# Buck_converter_demo.net
KiCad netlist of a schematic drawn in Altium Designer
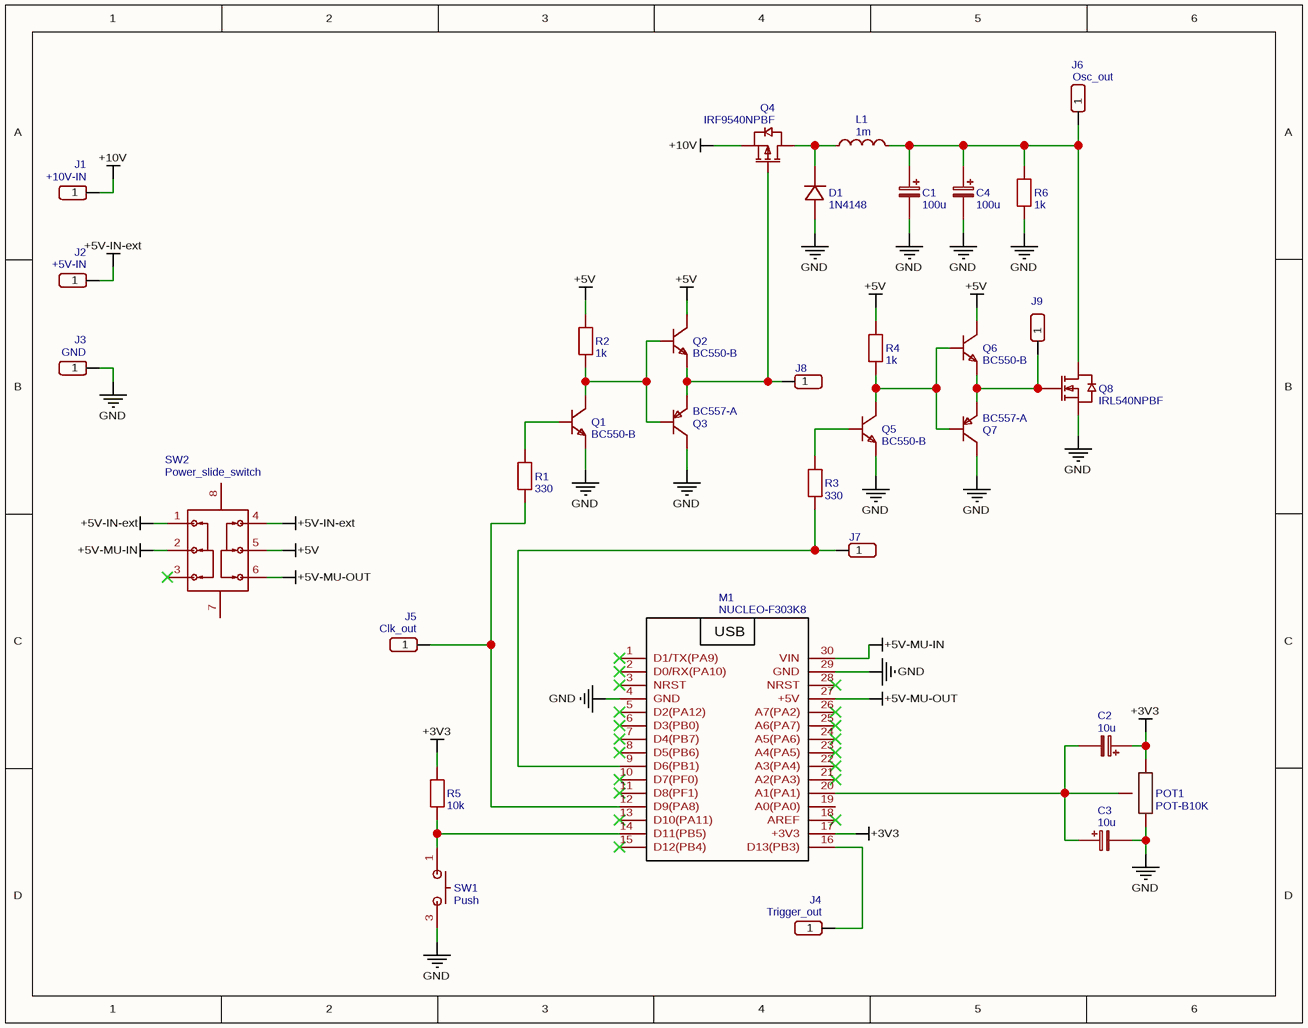
[diagram p0: Buck converter demo.schdoc]

(export (version "E")
  (design (tool "Eeschema 10.0.6"))
  (components
    (comp (ref "C1")
      (value "100u")
      (fields (field (name "CONTRIBUTOR") "LCEDA_Lib"))
      (libsource (lib "altium-import") (part "root_3_100u_"))
    )
    (comp (ref "C2")
      (value "10u")
      (fields (field (name "CONTRIBUTOR") "LCEDA_Lib"))
      (libsource (lib "altium-import") (part "root_2_10u_"))
    )
    (comp (ref "C3")
      (value "10u")
      (fields (field (name "CONTRIBUTOR") "LCEDA_Lib"))
      (libsource (lib "altium-import") (part "root_0_10u_"))
    )
    (comp (ref "C4")
      (value "100u")
      (fields (field (name "CONTRIBUTOR") "LCEDA_Lib"))
      (libsource (lib "altium-import") (part "root_3_100u_"))
    )
    (comp (ref "D1")
      (value "1N4148")
      (fields (field (name "MANUFACTURER") "ST(先科)"))
      (libsource (lib "altium-import") (part "root_1_1N4148_"))
    )
    (comp (ref "J1")
      (value "+10V-IN")
      (fields (field (name "CONTRIBUTOR") "LCEDA_Lib"))
      (libsource (lib "altium-import") (part "root_0_+10V-IN_"))
    )
    (comp (ref "J2")
      (value "+5V-IN")
      (fields (field (name "CONTRIBUTOR") "LCEDA_Lib"))
      (libsource (lib "altium-import") (part "root_0_+5V-IN_"))
    )
    (comp (ref "J3")
      (value "GND")
      (fields (field (name "CONTRIBUTOR") "LCEDA_Lib"))
      (libsource (lib "altium-import") (part "root_0_GND_"))
    )
    (comp (ref "J4")
      (value "Trigger_out")
      (fields (field (name "CONTRIBUTOR") "LCEDA_Lib"))
      (libsource (lib "altium-import") (part "root_0_Trigger_out_"))
    )
    (comp (ref "J5")
      (value "Clk_out")
      (fields (field (name "CONTRIBUTOR") "LCEDA_Lib"))
      (libsource (lib "altium-import") (part "root_0_Clk_out_"))
    )
    (comp (ref "J6")
      (value "Osc_out")
      (fields (field (name "CONTRIBUTOR") "LCEDA_Lib"))
      (libsource (lib "altium-import") (part "root_3_Osc_out_"))
    )
    (comp (ref "J7")
      (value "Osc_out")
      (fields (field (name "CONTRIBUTOR") "LCEDA_Lib"))
      (libsource (lib "altium-import") (part "root_2_Osc_out_"))
    )
    (comp (ref "J8")
      (value "Osc_out")
      (fields (field (name "CONTRIBUTOR") "LCEDA_Lib"))
      (libsource (lib "altium-import") (part "root_2_Osc_out_"))
    )
    (comp (ref "J9")
      (value "Osc_out")
      (fields (field (name "CONTRIBUTOR") "LCEDA_Lib"))
      (libsource (lib "altium-import") (part "root_3_Osc_out_"))
    )
    (comp (ref "L1")
      (value "1m")
      (fields (field (name "CONTRIBUTOR") "LCEDA_Lib"))
      (libsource (lib "altium-import") (part "root_0_1m_"))
    )
    (comp (ref "M1")
      (value "NUCLEO-F303K8")
      (fields (field (name "CONTRIBUTOR") "dleval"))
      (libsource (lib "altium-import") (part "root_0_NUCLEO-F303K8_"))
    )
    (comp (ref "POT1")
      (value "POT-B10K")
      (fields (field (name "CONTRIBUTOR") "Andrius Paurys"))
      (libsource (lib "altium-import") (part "root_1_POT-B10K_"))
    )
    (comp (ref "Q1")
      (value "BC550-B")
      (fields (field (name "MANUFACTURER") "BLUE ROCKET(蓝箭)") (field (name "CONTRIBUTOR") "LCSC"))
      (libsource (lib "altium-import") (part "root_0_BC550-B_"))
    )
    (comp (ref "Q2")
      (value "BC550-B")
      (fields (field (name "MANUFACTURER") "BLUE ROCKET(蓝箭)") (field (name "CONTRIBUTOR") "LCSC"))
      (libsource (lib "altium-import") (part "root_0_BC550-B_"))
    )
    (comp (ref "Q3")
      (value "BC557-A")
      (fields
        (field (name "MANUFACTURER") "onsemi(安森美)")
        (field (name "MANUFACTURER PART") "BC560CTA")
        (field (name "CONTRIBUTOR") "LCSC")
      )
      (libsource (lib "altium-import") (part "root_0_BC557-A_"))
    )
    (comp (ref "Q4")
      (value "IRF9540NPBF")
      (fields (field (name "MANUFACTURER") "Infineon(英飞凌)"))
      (libsource (lib "altium-import") (part "root_1_IRF9540NPBF_"))
    )
    (comp (ref "Q5")
      (value "BC550-B")
      (fields (field (name "MANUFACTURER") "BLUE ROCKET(蓝箭)") (field (name "CONTRIBUTOR") "LCSC"))
      (libsource (lib "altium-import") (part "root_0_BC550-B_"))
    )
    (comp (ref "Q6")
      (value "BC550-B")
      (fields (field (name "MANUFACTURER") "BLUE ROCKET(蓝箭)") (field (name "CONTRIBUTOR") "LCSC"))
      (libsource (lib "altium-import") (part "root_0_BC550-B_"))
    )
    (comp (ref "Q7")
      (value "BC557-A")
      (fields
        (field (name "MANUFACTURER") "onsemi(安森美)")
        (field (name "MANUFACTURER PART") "BC560CTA")
        (field (name "CONTRIBUTOR") "LCSC")
      )
      (libsource (lib "altium-import") (part "root_0_BC557-A_"))
    )
    (comp (ref "Q8")
      (value "IRL540NPBF")
      (fields (field (name "MANUFACTURER") "Infineon(英飞凌)"))
      (libsource (lib "altium-import") (part "root_0_IRL540NPBF_"))
    )
    (comp (ref "R1")
      (value "330")
      (fields (field (name "CONTRIBUTOR") "LCEDA_Lib"))
      (libsource (lib "altium-import") (part "root_1_330_"))
    )
    (comp (ref "R2")
      (value "1k")
      (fields (field (name "CONTRIBUTOR") "LCEDA_Lib"))
      (libsource (lib "altium-import") (part "root_1_1k_"))
    )
    (comp (ref "R3")
      (value "330")
      (fields (field (name "CONTRIBUTOR") "LCEDA_Lib"))
      (libsource (lib "altium-import") (part "root_1_330_"))
    )
    (comp (ref "R4")
      (value "1k")
      (fields (field (name "CONTRIBUTOR") "LCEDA_Lib"))
      (libsource (lib "altium-import") (part "root_1_1k_"))
    )
    (comp (ref "R5")
      (value "10k")
      (fields (field (name "CONTRIBUTOR") "LCEDA_Lib"))
      (libsource (lib "altium-import") (part "root_1_10k_"))
    )
    (comp (ref "R6")
      (value "1k")
      (fields (field (name "CONTRIBUTOR") "LCEDA_Lib"))
      (libsource (lib "altium-import") (part "root_1_1k_"))
    )
    (comp (ref "SW1")
      (value "Push")
      (fields
        (field (name "MANUFACTURER") "E-Switch")
        (field (name "MANUFACTURER PART") "800AWSP9M2QE")
        (field (name "CONTRIBUTOR") "LCSC")
      )
      (libsource (lib "altium-import") (part "root_3_Push_"))
    )
    (comp (ref "SW2")
      (value "Power_slide_switch")
      (fields
        (field (name "MANUFACTURER") "kinghelm(金航标)")
        (field (name "MANUFACTURER PART") "KH-SK22D07-G5")
        (field (name "CONTRIBUTOR") "lcsc")
      )
      (libsource (lib "altium-import") (part "root_3_Power_slide_switch_"))
    )
  )
  (nets
    (net (code "1") (name "+3V3") (class "Default")
      (node (ref "C2") (pin "1") (pinfunction "1_1") (pintype "passive"))
      (node (ref "M1") (pin "17") (pinfunction "+3V3_17") (pintype "passive"))
      (node (ref "POT1") (pin "2") (pinfunction "2_2") (pintype "passive"))
      (node (ref "R5") (pin "2") (pinfunction "2_2") (pintype "passive"))
    )
    (net (code "2") (name "+5V") (class "Default")
      (node (ref "Q2") (pin "3") (pinfunction "C_3") (pintype "passive"))
      (node (ref "Q6") (pin "3") (pinfunction "C_3") (pintype "passive"))
      (node (ref "R2") (pin "2") (pinfunction "2_2") (pintype "passive"))
      (node (ref "R4") (pin "2") (pinfunction "2_2") (pintype "passive"))
      (node (ref "SW2") (pin "5") (pinfunction "5_5") (pintype "passive"))
    )
    (net (code "3") (name "+5V-IN-ext") (class "Default")
      (node (ref "J2") (pin "1") (pinfunction "1_1") (pintype "passive"))
      (node (ref "SW2") (pin "1") (pinfunction "1_1") (pintype "passive"))
      (node (ref "SW2") (pin "4") (pinfunction "4_4") (pintype "passive"))
    )
    (net (code "4") (name "+5V-MU-IN") (class "Default")
      (node (ref "M1") (pin "30") (pinfunction "VIN_30") (pintype "passive"))
      (node (ref "SW2") (pin "2") (pinfunction "2_2") (pintype "passive"))
    )
    (net (code "5") (name "+5V-MU-OUT") (class "Default")
      (node (ref "M1") (pin "27") (pinfunction "+5V_27") (pintype "passive"))
      (node (ref "SW2") (pin "6") (pinfunction "6_6") (pintype "passive"))
    )
    (net (code "6") (name "+10V") (class "Default")
      (node (ref "J1") (pin "1") (pinfunction "1_1") (pintype "passive"))
      (node (ref "Q4") (pin "3") (pinfunction "S_3") (pintype "passive"))
    )
    (net (code "7") (name "GND") (class "Default")
      (node (ref "C1") (pin "2") (pinfunction "2_2") (pintype "passive"))
      (node (ref "C3") (pin "2") (pinfunction "2_2") (pintype "passive"))
      (node (ref "C4") (pin "2") (pinfunction "2_2") (pintype "passive"))
      (node (ref "D1") (pin "1") (pinfunction "A_1") (pintype "passive"))
      (node (ref "J3") (pin "1") (pinfunction "1_1") (pintype "passive"))
      (node (ref "M1") (pin "29") (pinfunction "GND_29") (pintype "passive"))
      (node (ref "M1") (pin "4") (pinfunction "GND_4") (pintype "passive"))
      (node (ref "POT1") (pin "1") (pinfunction "1_1") (pintype "passive"))
      (node (ref "Q1") (pin "1") (pinfunction "E_1") (pintype "passive"))
      (node (ref "Q3") (pin "1") (pinfunction "C_1") (pintype "passive"))
      (node (ref "Q5") (pin "1") (pinfunction "E_1") (pintype "passive"))
      (node (ref "Q7") (pin "1") (pinfunction "C_1") (pintype "passive"))
      (node (ref "Q8") (pin "3") (pinfunction "S_3") (pintype "passive"))
      (node (ref "R6") (pin "1") (pinfunction "1_1") (pintype "passive"))
      (node (ref "SW1") (pin "3") (pinfunction "3_3") (pintype "passive"))
    )
    (net (code "8") (name "Net-(D1-C)") (class "Default")
      (node (ref "D1") (pin "2") (pinfunction "C_2") (pintype "passive"))
      (node (ref "L1") (pin "1") (pinfunction "1_1") (pintype "passive"))
      (node (ref "Q4") (pin "2") (pinfunction "D_2") (pintype "passive"))
    )
    (net (code "9") (name "Net-(M1-A1(PA1))") (class "Default")
      (node (ref "C2") (pin "2") (pinfunction "2_2") (pintype "passive"))
      (node (ref "C3") (pin "1") (pinfunction "1_1") (pintype "passive"))
      (node (ref "M1") (pin "20") (pinfunction "A1(PA1)_20") (pintype "passive"))
      (node (ref "POT1") (pin "3") (pinfunction "3_3") (pintype "passive"))
    )
    (net (code "10") (name "Net-(M1-D6(PB1))") (class "Default")
      (node (ref "J7") (pin "1") (pinfunction "1_1") (pintype "passive"))
      (node (ref "M1") (pin "9") (pinfunction "D6(PB1)_9") (pintype "passive"))
      (node (ref "R3") (pin "1") (pinfunction "1_1") (pintype "passive"))
    )
    (net (code "11") (name "Net-(M1-D9(PA8))") (class "Default")
      (node (ref "J5") (pin "1") (pinfunction "1_1") (pintype "passive"))
      (node (ref "M1") (pin "12") (pinfunction "D9(PA8)_12") (pintype "passive"))
      (node (ref "R1") (pin "1") (pinfunction "1_1") (pintype "passive"))
    )
    (net (code "12") (name "Net-(M1-D11(PB5))") (class "Default")
      (node (ref "M1") (pin "14") (pinfunction "D11(PB5)_14") (pintype "passive"))
      (node (ref "R5") (pin "1") (pinfunction "1_1") (pintype "passive"))
      (node (ref "SW1") (pin "1") (pinfunction "1_1") (pintype "passive"))
    )
    (net (code "13") (name "Net-(M1-D13(PB3))") (class "Default")
      (node (ref "J4") (pin "1") (pinfunction "1_1") (pintype "passive"))
      (node (ref "M1") (pin "16") (pinfunction "D13(PB3)_16") (pintype "passive"))
    )
    (net (code "14") (name "Net-(Q1-B)") (class "Default")
      (node (ref "Q1") (pin "2") (pinfunction "B_2") (pintype "passive"))
      (node (ref "R1") (pin "2") (pinfunction "2_2") (pintype "passive"))
    )
    (net (code "15") (name "Net-(Q1-C)") (class "Default")
      (node (ref "Q1") (pin "3") (pinfunction "C_3") (pintype "passive"))
      (node (ref "Q2") (pin "2") (pinfunction "B_2") (pintype "passive"))
      (node (ref "Q3") (pin "2") (pinfunction "B_2") (pintype "passive"))
      (node (ref "R2") (pin "1") (pinfunction "1_1") (pintype "passive"))
    )
    (net (code "16") (name "Net-(Q2-E)") (class "Default")
      (node (ref "J8") (pin "1") (pinfunction "1_1") (pintype "passive"))
      (node (ref "Q2") (pin "1") (pinfunction "E_1") (pintype "passive"))
      (node (ref "Q3") (pin "3") (pinfunction "E_3") (pintype "passive"))
      (node (ref "Q4") (pin "1") (pinfunction "G_1") (pintype "passive"))
    )
    (net (code "17") (name "Net-(Q5-B)") (class "Default")
      (node (ref "Q5") (pin "2") (pinfunction "B_2") (pintype "passive"))
      (node (ref "R3") (pin "2") (pinfunction "2_2") (pintype "passive"))
    )
    (net (code "18") (name "Net-(Q5-C)") (class "Default")
      (node (ref "Q5") (pin "3") (pinfunction "C_3") (pintype "passive"))
      (node (ref "Q6") (pin "2") (pinfunction "B_2") (pintype "passive"))
      (node (ref "Q7") (pin "2") (pinfunction "B_2") (pintype "passive"))
      (node (ref "R4") (pin "1") (pinfunction "1_1") (pintype "passive"))
    )
    (net (code "19") (name "Net-(Q6-E)") (class "Default")
      (node (ref "J9") (pin "1") (pinfunction "1_1") (pintype "passive"))
      (node (ref "Q6") (pin "1") (pinfunction "E_1") (pintype "passive"))
      (node (ref "Q7") (pin "3") (pinfunction "E_3") (pintype "passive"))
      (node (ref "Q8") (pin "1") (pinfunction "G_1") (pintype "passive"))
    )
    (net (code "20") (name "Net-(Q8-D)") (class "Default")
      (node (ref "C1") (pin "1") (pinfunction "1_1") (pintype "passive"))
      (node (ref "C4") (pin "1") (pinfunction "1_1") (pintype "passive"))
      (node (ref "J6") (pin "1") (pinfunction "1_1") (pintype "passive"))
      (node (ref "L1") (pin "2") (pinfunction "2_2") (pintype "passive"))
      (node (ref "Q8") (pin "2") (pinfunction "D_2") (pintype "passive"))
      (node (ref "R6") (pin "2") (pinfunction "2_2") (pintype "passive"))
    )
    (net (code "21") (name "unconnected-(M1-A0(PA0)-Pad19)") (class "Default")
      (node (ref "M1") (pin "19") (pinfunction "A0(PA0)_19") (pintype "passive"))
    )
    (net (code "22") (name "unconnected-(M1-A2(PA3)-Pad21)") (class "Default")
      (node (ref "M1") (pin "21") (pinfunction "A2(PA3)_21") (pintype "passive+no_connect"))
    )
    (net (code "23") (name "unconnected-(M1-A3(PA4)-Pad22)") (class "Default")
      (node (ref "M1") (pin "22") (pinfunction "A3(PA4)_22") (pintype "passive+no_connect"))
    )
    (net (code "24") (name "unconnected-(M1-A4(PA5)-Pad23)") (class "Default")
      (node (ref "M1") (pin "23") (pinfunction "A4(PA5)_23") (pintype "passive+no_connect"))
    )
    (net (code "25") (name "unconnected-(M1-A5(PA6)-Pad24)") (class "Default")
      (node (ref "M1") (pin "24") (pinfunction "A5(PA6)_24") (pintype "passive+no_connect"))
    )
    (net (code "26") (name "unconnected-(M1-A6(PA7)-Pad25)") (class "Default")
      (node (ref "M1") (pin "25") (pinfunction "A6(PA7)_25") (pintype "passive+no_connect"))
    )
    (net (code "27") (name "unconnected-(M1-A7(PA2)-Pad26)") (class "Default")
      (node (ref "M1") (pin "26") (pinfunction "A7(PA2)_26") (pintype "passive+no_connect"))
    )
    (net (code "28") (name "unconnected-(M1-AREF-Pad18)") (class "Default")
      (node (ref "M1") (pin "18") (pinfunction "AREF_18") (pintype "passive+no_connect"))
    )
    (net (code "29") (name "unconnected-(M1-D0{slash}RX(PA10)-Pad2)") (class "Default")
      (node (ref "M1") (pin "2") (pinfunction "D0/RX(PA10)_2") (pintype "passive+no_connect"))
    )
    (net (code "30") (name "unconnected-(M1-D1{slash}TX(PA9)-Pad1)") (class "Default")
      (node (ref "M1") (pin "1") (pinfunction "D1/TX(PA9)_1") (pintype "passive+no_connect"))
    )
    (net (code "31") (name "unconnected-(M1-D2(PA12)-Pad5)") (class "Default")
      (node (ref "M1") (pin "5") (pinfunction "D2(PA12)_5") (pintype "passive+no_connect"))
    )
    (net (code "32") (name "unconnected-(M1-D3(PB0)-Pad6)") (class "Default")
      (node (ref "M1") (pin "6") (pinfunction "D3(PB0)_6") (pintype "passive+no_connect"))
    )
    (net (code "33") (name "unconnected-(M1-D4(PB7)-Pad7)") (class "Default")
      (node (ref "M1") (pin "7") (pinfunction "D4(PB7)_7") (pintype "passive+no_connect"))
    )
    (net (code "34") (name "unconnected-(M1-D5(PB6)-Pad8)") (class "Default")
      (node (ref "M1") (pin "8") (pinfunction "D5(PB6)_8") (pintype "passive+no_connect"))
    )
    (net (code "35") (name "unconnected-(M1-D7(PF0)-Pad10)") (class "Default")
      (node (ref "M1") (pin "10") (pinfunction "D7(PF0)_10") (pintype "passive+no_connect"))
    )
    (net (code "36") (name "unconnected-(M1-D8(PF1)-Pad11)") (class "Default")
      (node (ref "M1") (pin "11") (pinfunction "D8(PF1)_11") (pintype "passive+no_connect"))
    )
    (net (code "37") (name "unconnected-(M1-D10(PA11)-Pad13)") (class "Default")
      (node (ref "M1") (pin "13") (pinfunction "D10(PA11)_13") (pintype "passive+no_connect"))
    )
    (net (code "38") (name "unconnected-(M1-D12(PB4)-Pad15)") (class "Default")
      (node (ref "M1") (pin "15") (pinfunction "D12(PB4)_15") (pintype "passive+no_connect"))
    )
    (net (code "39") (name "unconnected-(M1-NRST-Pad3)") (class "Default")
      (node (ref "M1") (pin "3") (pinfunction "NRST_3") (pintype "passive+no_connect"))
    )
    (net (code "40") (name "unconnected-(M1-NRST-Pad28)") (class "Default")
      (node (ref "M1") (pin "28") (pinfunction "NRST_28") (pintype "passive+no_connect"))
    )
    (net (code "41") (name "unconnected-(SW2-Pad3)") (class "Default")
      (node (ref "SW2") (pin "3") (pinfunction "3_3") (pintype "passive+no_connect"))
    )
    (net (code "42") (name "unconnected-(SW2-Pad7)") (class "Default")
      (node (ref "SW2") (pin "7") (pinfunction "7_7") (pintype "passive"))
    )
    (net (code "43") (name "unconnected-(SW2-Pad8)") (class "Default")
      (node (ref "SW2") (pin "8") (pinfunction "8_8") (pintype "passive"))
    )
  )
)
